# CANLink.net
KiCad netlist of a schematic drawn in Altium Designer
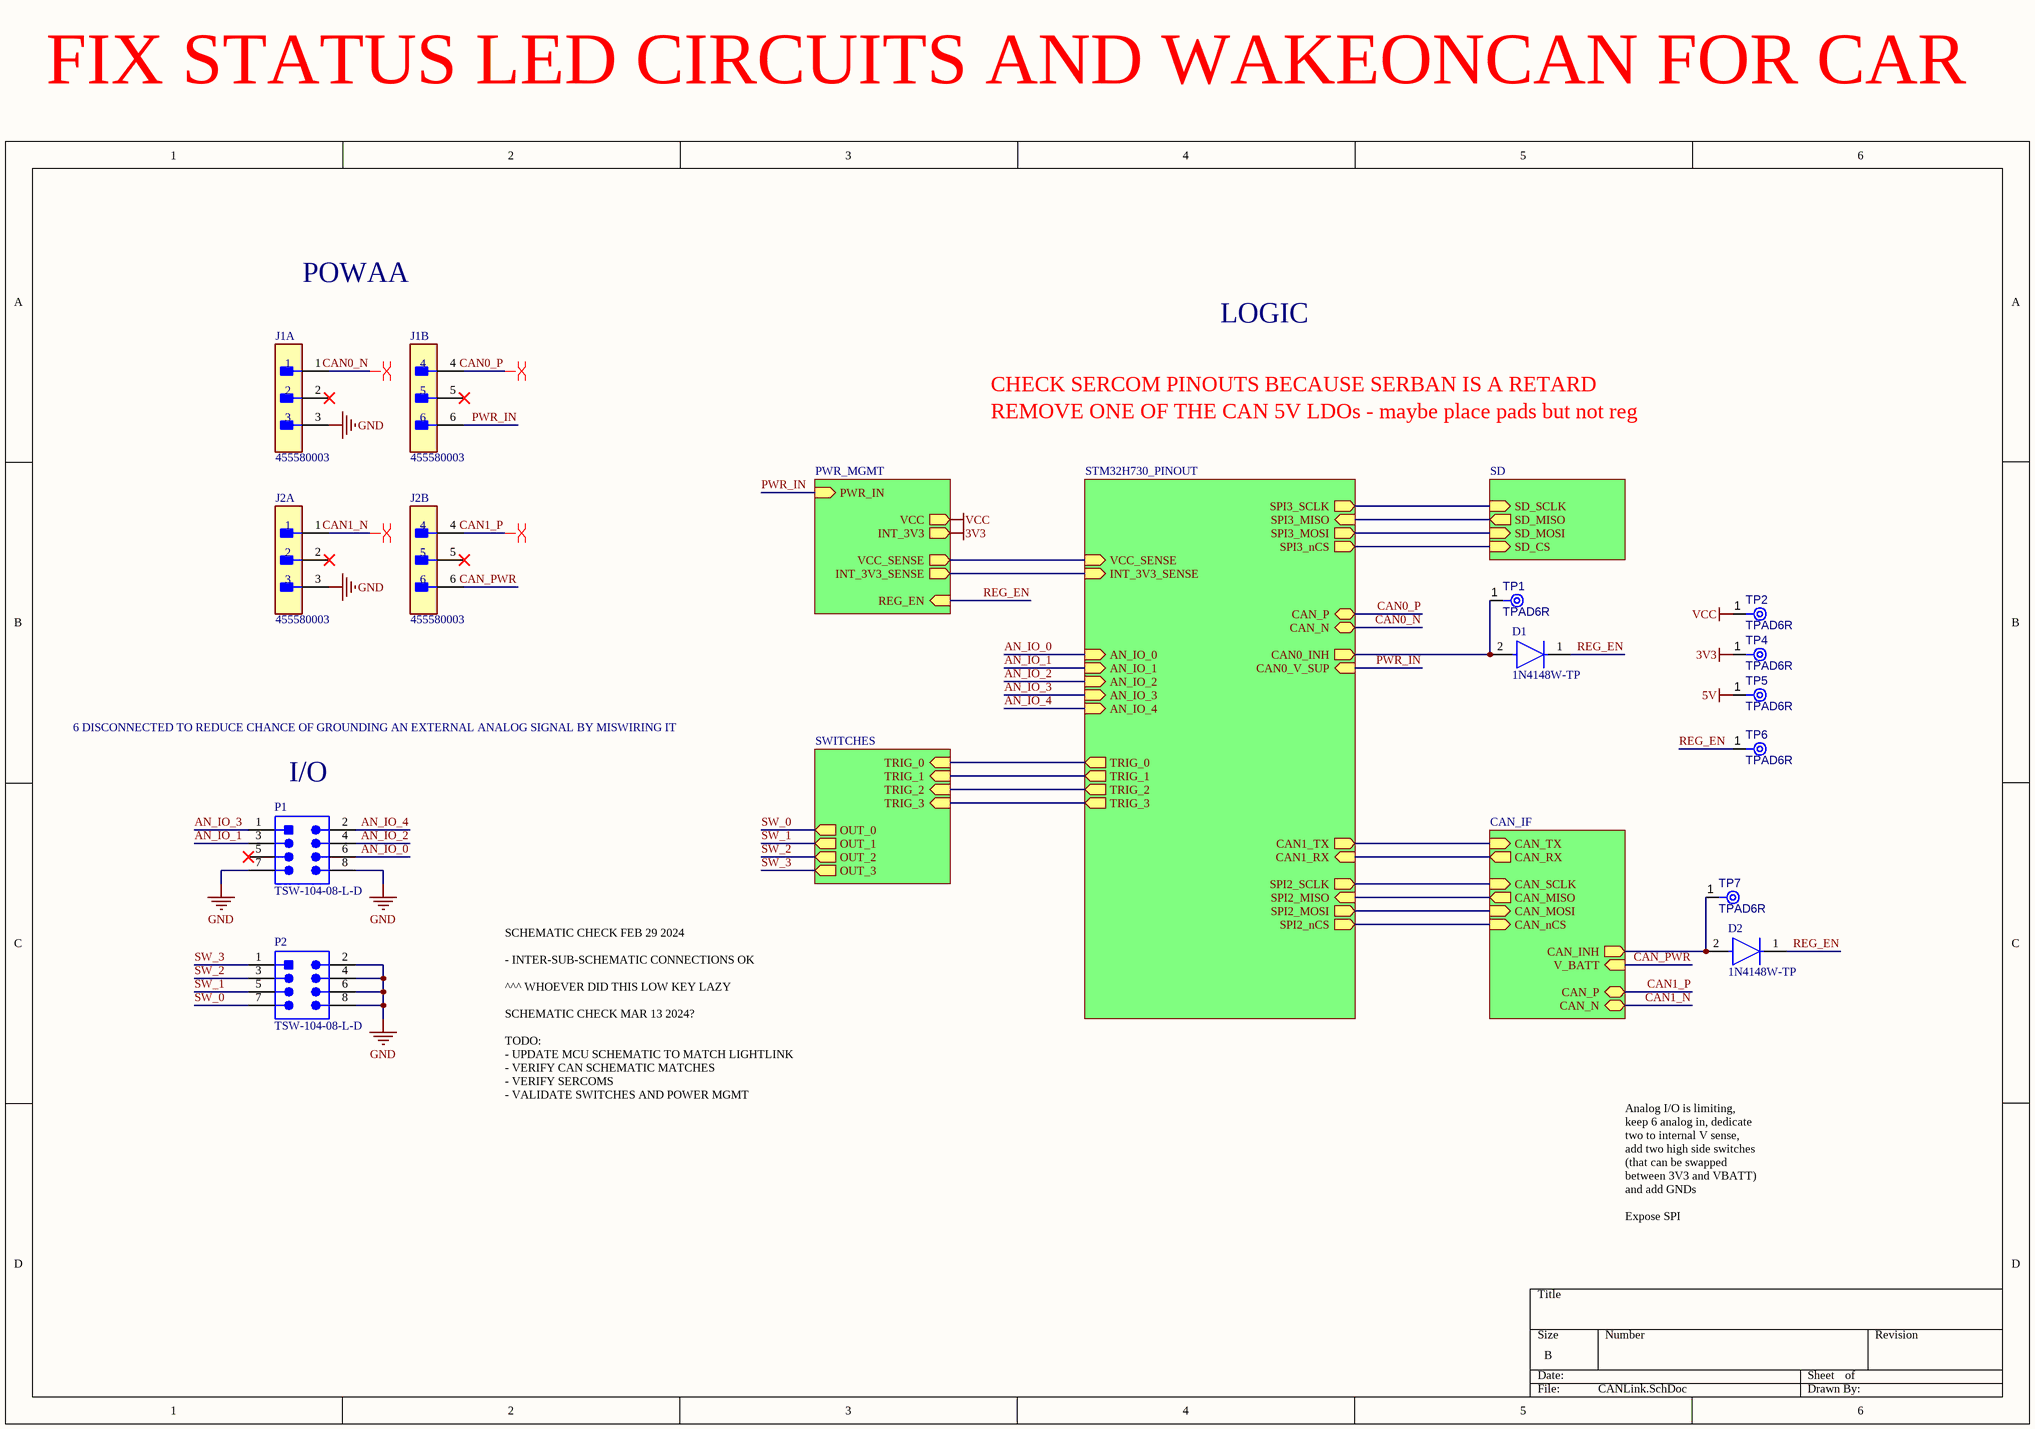
[diagram p0: CANLink.SchDoc]

(export (version "E")
  (design (tool "Eeschema 10.0.6"))
  (components
    (comp (ref "D1")
      (value "1N4148W-TP")
      (footprint "FP-SOD-123-IPC_A")
      (description "DIODE GEN PURP 100V 150MA SOD123")
      (libsource (lib "Altium Content Vault") (part "d7152d700b627762746794eb795d46e"))
    )
    (comp (ref "D2")
      (value "1N4148W-TP")
      (footprint "FP-SOD-123-IPC_A")
      (description "DIODE GEN PURP 100V 150MA SOD123")
      (libsource (lib "Altium Content Vault") (part "d7152d700b627762746794eb795d46e"))
    )
    (comp (ref "J1")
      (value "455580003")
      (footprint "FP-455580003-MFG")
      (description "CONN HEADER R/A 6POS 4.2MM")
      (fields
        (field (name "OCTOPART") "https://octopart.com/45558-0003-molex-7672845")
        (field (name "MANUFACTURER") "Molex")
      )
      (libsource (lib "Altium Content Vault") (part "bb9cbdb24149a20ba329b4e86909569"))
    )
    (comp (ref "J2")
      (value "455580003")
      (footprint "FP-455580003-MFG")
      (description "CONN HEADER R/A 6POS 4.2MM")
      (fields
        (field (name "OCTOPART") "https://octopart.com/45558-0003-molex-7672845")
        (field (name "MANUFACTURER") "Molex")
      )
      (libsource (lib "Altium Content Vault") (part "bb9cbdb24149a20ba329b4e86909569"))
    )
    (comp (ref "P1")
      (value "TSW-104-08-L-D")
      (footprint "SMTC-TSW-104-08-L-D_V")
      (fields (field (name "MANUFACTURER") "Samtec"))
      (libsource (lib "Altium Content Vault") (part "CN-2P-M-R8"))
    )
    (comp (ref "P2")
      (value "TSW-104-08-L-D")
      (footprint "SMTC-TSW-104-08-L-D_V")
      (fields (field (name "MANUFACTURER") "Samtec"))
      (libsource (lib "Altium Content Vault") (part "CN-2P-M-R8"))
    )
    (comp (ref "TP1")
      (value "TPAD6R")
      (footprint "TP06R")
      (description "0.6mm round")
      (libsource (lib "uORocketry Hardware") (part "CMP-001-0001-4"))
    )
    (comp (ref "TP2")
      (value "TPAD6R")
      (footprint "TP06R")
      (description "0.6mm round")
      (libsource (lib "uORocketry Hardware") (part "CMP-001-0001-4"))
    )
    (comp (ref "TP4")
      (value "TPAD6R")
      (footprint "TP06R")
      (description "0.6mm round")
      (libsource (lib "uORocketry Hardware") (part "CMP-001-0001-4"))
    )
    (comp (ref "TP5")
      (value "TPAD6R")
      (footprint "TP06R")
      (description "0.6mm round")
      (libsource (lib "uORocketry Hardware") (part "CMP-001-0001-4"))
    )
    (comp (ref "TP6")
      (value "TPAD6R")
      (footprint "TP06R")
      (description "0.6mm round")
      (libsource (lib "uORocketry Hardware") (part "CMP-001-0001-4"))
    )
    (comp (ref "TP7")
      (value "TPAD6R")
      (footprint "TP06R")
      (description "0.6mm round")
      (libsource (lib "uORocketry Hardware") (part "CMP-001-0001-4"))
    )
  )
  (nets
    (net (code "1") (name "/AN_IO_0") (class "Default")
      (node (ref "P1") (pin "6") (pinfunction "6_6") (pintype "passive"))
    )
    (net (code "2") (name "/AN_IO_1") (class "Default")
      (node (ref "P1") (pin "3") (pinfunction "3_3") (pintype "passive"))
    )
    (net (code "3") (name "/AN_IO_2") (class "Default")
      (node (ref "P1") (pin "4") (pinfunction "4_4") (pintype "passive"))
    )
    (net (code "4") (name "/AN_IO_3") (class "Default")
      (node (ref "P1") (pin "1") (pinfunction "1_1") (pintype "passive"))
    )
    (net (code "5") (name "/AN_IO_4") (class "Default")
      (node (ref "P1") (pin "2") (pinfunction "2_2") (pintype "passive"))
    )
    (net (code "6") (name "/CAN0_INH") (class "Default")
      (node (ref "D1") (pin "2") (pinfunction "A_2") (pintype "passive"))
      (node (ref "TP1") (pin "1") (pinfunction "TP_1") (pintype "passive"))
    )
    (net (code "7") (name "/CAN0_N") (class "Default")
      (node (ref "J1") (pin "1") (pinfunction "1_1") (pintype "passive"))
    )
    (net (code "8") (name "/CAN0_P") (class "Default")
      (node (ref "J1") (pin "4") (pinfunction "4_4") (pintype "passive"))
    )
    (net (code "9") (name "/CAN1_N") (class "Default")
      (node (ref "J2") (pin "1") (pinfunction "1_1") (pintype "passive"))
    )
    (net (code "10") (name "/CAN1_P") (class "Default")
      (node (ref "J2") (pin "4") (pinfunction "4_4") (pintype "passive"))
    )
    (net (code "12") (name "/CAN_INH") (class "Default")
      (node (ref "D2") (pin "2") (pinfunction "A_2") (pintype "passive"))
      (node (ref "TP7") (pin "1") (pinfunction "TP_1") (pintype "passive"))
    )
    (net (code "14") (name "/CAN_PWR") (class "Default")
      (node (ref "J2") (pin "6") (pinfunction "6_6") (pintype "passive"))
    )
    (net (code "17") (name "/PWR_IN") (class "Default")
      (node (ref "J1") (pin "6") (pinfunction "6_6") (pintype "passive"))
    )
    (net (code "18") (name "/REG_EN") (class "Default")
      (node (ref "D1") (pin "1") (pinfunction "C_1") (pintype "passive"))
      (node (ref "D2") (pin "1") (pinfunction "C_1") (pintype "passive"))
      (node (ref "TP6") (pin "1") (pinfunction "TP_1") (pintype "passive"))
    )
    (net (code "26") (name "/SW_0") (class "Default")
      (node (ref "P2") (pin "7") (pinfunction "7_7") (pintype "passive"))
    )
    (net (code "27") (name "/SW_1") (class "Default")
      (node (ref "P2") (pin "5") (pinfunction "5_5") (pintype "passive"))
    )
    (net (code "28") (name "/SW_2") (class "Default")
      (node (ref "P2") (pin "3") (pinfunction "3_3") (pintype "passive"))
    )
    (net (code "29") (name "/SW_3") (class "Default")
      (node (ref "P2") (pin "1") (pinfunction "1_1") (pintype "passive"))
    )
    (net (code "35") (name "3V3") (class "Default")
      (node (ref "TP4") (pin "1") (pinfunction "TP_1") (pintype "passive"))
    )
    (net (code "36") (name "5V") (class "Default")
      (node (ref "TP5") (pin "1") (pinfunction "TP_1") (pintype "passive"))
    )
    (net (code "37") (name "GND") (class "Default")
      (node (ref "J1") (pin "3") (pinfunction "3_3") (pintype "passive"))
      (node (ref "J2") (pin "3") (pinfunction "3_3") (pintype "passive"))
      (node (ref "P1") (pin "7") (pinfunction "7_7") (pintype "passive"))
      (node (ref "P1") (pin "8") (pinfunction "8_8") (pintype "passive"))
      (node (ref "P2") (pin "2") (pinfunction "2_2") (pintype "passive"))
      (node (ref "P2") (pin "4") (pinfunction "4_4") (pintype "passive"))
      (node (ref "P2") (pin "6") (pinfunction "6_6") (pintype "passive"))
      (node (ref "P2") (pin "8") (pinfunction "8_8") (pintype "passive"))
    )
    (net (code "38") (name "VCC") (class "Default")
      (node (ref "TP2") (pin "1") (pinfunction "TP_1") (pintype "passive"))
    )
    (net (code "39") (name "unconnected-(J1-Pad2)") (class "Default")
      (node (ref "J1") (pin "2") (pinfunction "2_2") (pintype "passive+no_connect"))
    )
    (net (code "40") (name "unconnected-(J1-Pad5)") (class "Default")
      (node (ref "J1") (pin "5") (pinfunction "5_5") (pintype "passive+no_connect"))
    )
    (net (code "41") (name "unconnected-(J2-Pad2)") (class "Default")
      (node (ref "J2") (pin "2") (pinfunction "2_2") (pintype "passive+no_connect"))
    )
    (net (code "42") (name "unconnected-(J2-Pad5)") (class "Default")
      (node (ref "J2") (pin "5") (pinfunction "5_5") (pintype "passive+no_connect"))
    )
    (net (code "43") (name "unconnected-(P1-Pad5)") (class "Default")
      (node (ref "P1") (pin "5") (pinfunction "5_5") (pintype "passive+no_connect"))
    )
  )
)
